# Sensor_Board_AS-3.net
KiCad netlist of a schematic drawn in EAGLE
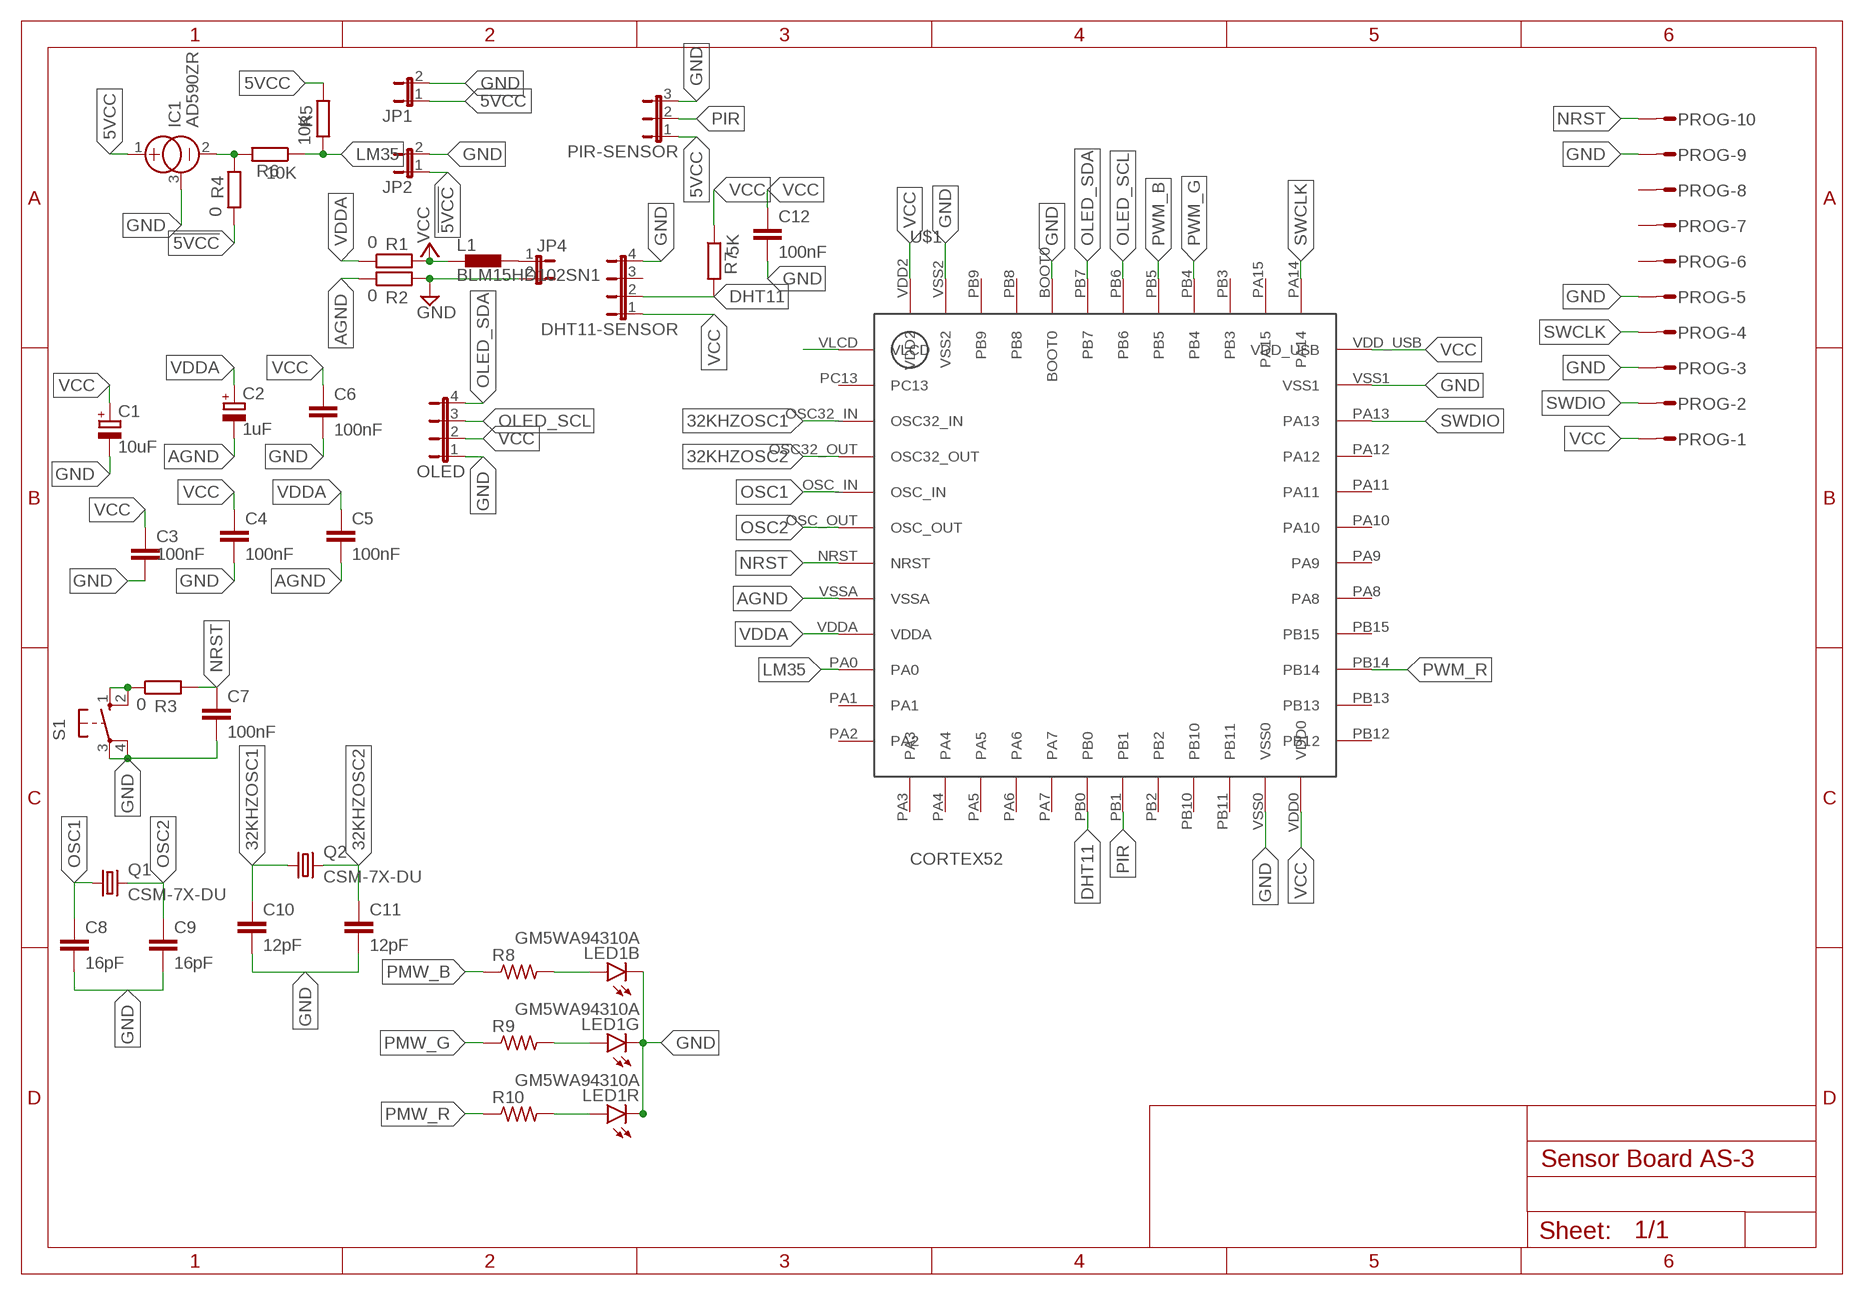
[diagram p0: schematic, sheet 1]

(export (version "E")
  (design (tool "Eeschema 10.0.6"))
  (components
    (comp (ref "C1")
      (value "10uF")
      (footprint "eagle-import:139CLL-2R")
      (libsource (lib "eagle-import") (part "CPOL-EU139CLL-2R"))
    )
    (comp (ref "C2")
      (value "1uF")
      (footprint "eagle-import:139CLL-2R")
      (libsource (lib "eagle-import") (part "CPOL-EU139CLL-2R"))
    )
    (comp (ref "C3")
      (value "100nF")
      (footprint "eagle-import:C0805")
      (libsource (lib "eagle-import") (part "C-EUC0805"))
    )
    (comp (ref "C4")
      (value "100nF")
      (footprint "eagle-import:C0805")
      (libsource (lib "eagle-import") (part "C-EUC0805"))
    )
    (comp (ref "C5")
      (value "100nF")
      (footprint "eagle-import:C0805")
      (libsource (lib "eagle-import") (part "C-EUC0805"))
    )
    (comp (ref "C6")
      (value "100nF")
      (footprint "eagle-import:C0805")
      (libsource (lib "eagle-import") (part "C-EUC0805"))
    )
    (comp (ref "C7")
      (value "100nF")
      (footprint "eagle-import:C0805")
      (libsource (lib "eagle-import") (part "C-EUC0805"))
    )
    (comp (ref "C8")
      (value "16pF")
      (footprint "eagle-import:C0805")
      (libsource (lib "eagle-import") (part "C-EUC0805"))
    )
    (comp (ref "C9")
      (value "16pF")
      (footprint "eagle-import:C0805")
      (libsource (lib "eagle-import") (part "C-EUC0805"))
    )
    (comp (ref "C10")
      (value "12pF")
      (footprint "eagle-import:C0805")
      (libsource (lib "eagle-import") (part "C-EUC0805"))
    )
    (comp (ref "C11")
      (value "12pF")
      (footprint "eagle-import:C0805")
      (libsource (lib "eagle-import") (part "C-EUC0805"))
    )
    (comp (ref "C12")
      (value "100nF")
      (footprint "eagle-import:C0805")
      (libsource (lib "eagle-import") (part "C-EUC0805"))
    )
    (comp (ref "DHT11-SENSOR")
      (value "JP4E")
      (footprint "eagle-import:JP4")
      (libsource (lib "eagle-import") (part "JP4E"))
    )
    (comp (ref "IC1")
      (value "AD590ZR")
      (footprint "eagle-import:TO92")
      (libsource (lib "eagle-import") (part "AD590ZR"))
    )
    (comp (ref "JP1")
      (value "JP1E")
      (footprint "eagle-import:JP1")
      (libsource (lib "eagle-import") (part "JP1E"))
    )
    (comp (ref "JP2")
      (value "JP1E")
      (footprint "eagle-import:JP1")
      (libsource (lib "eagle-import") (part "JP1E"))
    )
    (comp (ref "JP4")
      (value "JP1E")
      (footprint "eagle-import:JP1")
      (libsource (lib "eagle-import") (part "JP1E"))
    )
    (comp (ref "L1")
      (value "BLM15HD102SN1")
      (footprint "eagle-import:0402")
      (libsource (lib "eagle-import") (part "BLM15HD102SN1"))
    )
    (comp (ref "LED1")
      (value "GM5WA94310A")
      (footprint "eagle-import:GM5WA94310A")
      (libsource (lib "eagle-import") (part "GM5WA94310A"))
    )
    (comp (ref "OLED")
      (value "JP4E")
      (footprint "eagle-import:JP4")
      (libsource (lib "eagle-import") (part "JP4E"))
    )
    (comp (ref "PIR-SENSOR")
      (value "JP2E")
      (footprint "eagle-import:JP2")
      (libsource (lib "eagle-import") (part "JP2E"))
    )
    (comp (ref "PROG")
      (value "S10P")
      (footprint "eagle-import:S10P")
      (libsource (lib "eagle-import") (part "S10P"))
    )
    (comp (ref "Q1")
      (value "CSM-7X-DU")
      (footprint "eagle-import:CSM-7X-DU")
      (libsource (lib "eagle-import") (part "CSM-7X-DU"))
    )
    (comp (ref "Q2")
      (value "CSM-7X-DU")
      (footprint "eagle-import:CSM-7X-DU")
      (libsource (lib "eagle-import") (part "CSM-7X-DU"))
    )
    (comp (ref "R1")
      (value "0")
      (footprint "eagle-import:R0805")
      (libsource (lib "eagle-import") (part "R-EU_R0805"))
    )
    (comp (ref "R2")
      (value "0")
      (footprint "eagle-import:R0805")
      (libsource (lib "eagle-import") (part "R-EU_R0805"))
    )
    (comp (ref "R3")
      (value "0")
      (footprint "eagle-import:R0805")
      (libsource (lib "eagle-import") (part "R-EU_R0805"))
    )
    (comp (ref "R4")
      (value "0")
      (footprint "eagle-import:R0805")
      (libsource (lib "eagle-import") (part "R-EU_R0805"))
    )
    (comp (ref "R5")
      (value "10K")
      (footprint "eagle-import:R0805")
      (libsource (lib "eagle-import") (part "R-EU_R0805"))
    )
    (comp (ref "R6")
      (value "10K")
      (footprint "eagle-import:R0805")
      (libsource (lib "eagle-import") (part "R-EU_R0805"))
    )
    (comp (ref "R7")
      (value "5K")
      (footprint "eagle-import:R0805")
      (libsource (lib "eagle-import") (part "R-EU_R0805"))
    )
    (comp (ref "R8")
      (value "R-US_R0805")
      (footprint "eagle-import:R0805")
      (libsource (lib "eagle-import") (part "R-US_R0805"))
    )
    (comp (ref "R9")
      (value "R-US_R0805")
      (footprint "eagle-import:R0805")
      (libsource (lib "eagle-import") (part "R-US_R0805"))
    )
    (comp (ref "R10")
      (value "R-US_R0805")
      (footprint "eagle-import:R0805")
      (libsource (lib "eagle-import") (part "R-US_R0805"))
    )
    (comp (ref "S1")
      (value "10-XX")
      (footprint "eagle-import:B3F-10XX")
      (fields (field (name "MPN") "B3F-1000"))
      (libsource (lib "eagle-import") (part "10-XX"))
    )
    (comp (ref "U$1")
      (value "CORTEX52")
      (footprint "eagle-import:CORTEX52")
      (libsource (lib "eagle-import") (part "CORTEX52"))
    )
  )
  (nets
    (net (code "1") (name "/~{5VCC}") (class "Default")
      (node (ref "JP2") (pin "1") (pinfunction "1_1") (pintype "passive"))
      (node (ref "R4") (pin "1") (pinfunction "1_1") (pintype "passive"))
    )
    (net (code "2") (name "5VCC") (class "Default")
      (node (ref "IC1") (pin "1") (pinfunction "+_1") (pintype "input"))
      (node (ref "JP1") (pin "1") (pinfunction "1_1") (pintype "passive"))
      (node (ref "PIR-SENSOR") (pin "1") (pinfunction "1_1") (pintype "passive"))
      (node (ref "R5") (pin "2") (pinfunction "2_2") (pintype "passive"))
    )
    (net (code "3") (name "32KHZOSC1") (class "Default")
      (node (ref "C10") (pin "1") (pinfunction "1_1") (pintype "passive"))
      (node (ref "Q2") (pin "1") (pinfunction "1_1") (pintype "passive"))
      (node (ref "U$1") (pin "OSC32_IN") (pinfunction "OSC32_IN_OSC32_IN") (pintype "bidirectional"))
    )
    (net (code "4") (name "32KHZOSC2") (class "Default")
      (node (ref "C11") (pin "1") (pinfunction "1_1") (pintype "passive"))
      (node (ref "Q2") (pin "2") (pinfunction "2_2") (pintype "passive"))
      (node (ref "U$1") (pin "OSC32_OUT") (pinfunction "OSC32_OUT_OSC32_OUT") (pintype "bidirectional"))
    )
    (net (code "5") (name "AGND") (class "Default")
      (node (ref "C2") (pin "-") (pinfunction "-_-") (pintype "passive"))
      (node (ref "C5") (pin "2") (pinfunction "2_2") (pintype "passive"))
      (node (ref "R2") (pin "1") (pinfunction "1_1") (pintype "passive"))
      (node (ref "U$1") (pin "VSSA") (pinfunction "VSSA_VSSA") (pintype "bidirectional"))
    )
    (net (code "6") (name "DHT11") (class "Default")
      (node (ref "DHT11-SENSOR") (pin "2") (pinfunction "2_2") (pintype "passive"))
      (node (ref "R7") (pin "2") (pinfunction "2_2") (pintype "passive"))
      (node (ref "U$1") (pin "PB0") (pinfunction "PB0_PB0") (pintype "bidirectional"))
    )
    (net (code "7") (name "GND") (class "Default")
      (node (ref "C1") (pin "-") (pinfunction "-_-") (pintype "passive"))
      (node (ref "C10") (pin "2") (pinfunction "2_2") (pintype "passive"))
      (node (ref "C11") (pin "2") (pinfunction "2_2") (pintype "passive"))
      (node (ref "C12") (pin "2") (pinfunction "2_2") (pintype "passive"))
      (node (ref "C3") (pin "2") (pinfunction "2_2") (pintype "passive"))
      (node (ref "C4") (pin "2") (pinfunction "2_2") (pintype "passive"))
      (node (ref "C6") (pin "2") (pinfunction "2_2") (pintype "passive"))
      (node (ref "C7") (pin "2") (pinfunction "2_2") (pintype "passive"))
      (node (ref "C8") (pin "2") (pinfunction "2_2") (pintype "passive"))
      (node (ref "C9") (pin "2") (pinfunction "2_2") (pintype "passive"))
      (node (ref "DHT11-SENSOR") (pin "4") (pinfunction "4_4") (pintype "passive"))
      (node (ref "IC1") (pin "3") (pinfunction "CAN_3") (pintype "passive"))
      (node (ref "JP1") (pin "2") (pinfunction "2_2") (pintype "passive"))
      (node (ref "JP2") (pin "2") (pinfunction "2_2") (pintype "passive"))
      (node (ref "JP4") (pin "2") (pinfunction "2_2") (pintype "passive"))
      (node (ref "LED1") (pin "4") (pinfunction "C_4") (pintype "passive"))
      (node (ref "LED1") (pin "5") (pinfunction "C_5") (pintype "passive"))
      (node (ref "LED1") (pin "6") (pinfunction "C_6") (pintype "passive"))
      (node (ref "OLED") (pin "1") (pinfunction "1_1") (pintype "passive"))
      (node (ref "PIR-SENSOR") (pin "3") (pinfunction "3_3") (pintype "passive"))
      (node (ref "PROG") (pin "3") (pinfunction "S_3") (pintype "passive"))
      (node (ref "PROG") (pin "5") (pinfunction "S_5") (pintype "passive"))
      (node (ref "PROG") (pin "9") (pinfunction "S_9") (pintype "passive"))
      (node (ref "R2") (pin "2") (pinfunction "2_2") (pintype "passive"))
      (node (ref "S1") (pin "3") (pinfunction "P_3") (pintype "passive"))
      (node (ref "S1") (pin "4") (pinfunction "P1_4") (pintype "passive"))
      (node (ref "U$1") (pin "BOOT0") (pinfunction "BOOT0_BOOT0") (pintype "bidirectional"))
      (node (ref "U$1") (pin "VSS0") (pinfunction "VSS0_VSS0") (pintype "bidirectional"))
      (node (ref "U$1") (pin "VSS1") (pinfunction "VSS1_VSS1") (pintype "bidirectional"))
      (node (ref "U$1") (pin "VSS2") (pinfunction "VSS2_VSS2") (pintype "bidirectional"))
    )
    (net (code "8") (name "LM35") (class "Default")
      (node (ref "R5") (pin "1") (pinfunction "1_1") (pintype "passive"))
      (node (ref "R6") (pin "1") (pinfunction "1_1") (pintype "passive"))
      (node (ref "U$1") (pin "PA0") (pinfunction "PA0_PA0") (pintype "bidirectional"))
    )
    (net (code "9") (name "NRST") (class "Default")
      (node (ref "C7") (pin "1") (pinfunction "1_1") (pintype "passive"))
      (node (ref "PROG") (pin "10") (pinfunction "S_10") (pintype "passive"))
      (node (ref "R3") (pin "2") (pinfunction "2_2") (pintype "passive"))
      (node (ref "U$1") (pin "NRST") (pinfunction "NRST_NRST") (pintype "bidirectional"))
    )
    (net (code "10") (name "Net-(IC1--)") (class "Default")
      (node (ref "IC1") (pin "2") (pinfunction "-_2") (pintype "input"))
      (node (ref "R4") (pin "2") (pinfunction "2_2") (pintype "passive"))
      (node (ref "R6") (pin "2") (pinfunction "2_2") (pintype "passive"))
    )
    (net (code "11") (name "Net-(JP4-Pad1)") (class "Default")
      (node (ref "JP4") (pin "1") (pinfunction "1_1") (pintype "passive"))
      (node (ref "L1") (pin "2") (pinfunction "2_2") (pintype "passive"))
    )
    (net (code "12") (name "Net-(LED1A-A)") (class "Default")
      (node (ref "LED1") (pin "1") (pinfunction "A_1") (pintype "passive"))
      (node (ref "R8") (pin "2") (pinfunction "2_2") (pintype "passive"))
    )
    (net (code "13") (name "Net-(LED1B-A)") (class "Default")
      (node (ref "LED1") (pin "3") (pinfunction "A_3") (pintype "passive"))
      (node (ref "R9") (pin "2") (pinfunction "2_2") (pintype "passive"))
    )
    (net (code "14") (name "Net-(LED1C-A)") (class "Default")
      (node (ref "LED1") (pin "2") (pinfunction "A_2") (pintype "passive"))
      (node (ref "R10") (pin "2") (pinfunction "2_2") (pintype "passive"))
    )
    (net (code "15") (name "Net-(S1-S)") (class "Default")
      (node (ref "R3") (pin "1") (pinfunction "1_1") (pintype "passive"))
      (node (ref "S1") (pin "1") (pinfunction "S_1") (pintype "passive"))
      (node (ref "S1") (pin "2") (pinfunction "S1_2") (pintype "passive"))
    )
    (net (code "16") (name "OLED_SCL") (class "Default")
      (node (ref "OLED") (pin "3") (pinfunction "3_3") (pintype "passive"))
      (node (ref "U$1") (pin "PB6") (pinfunction "PB6_PB6") (pintype "bidirectional"))
    )
    (net (code "17") (name "OLED_SDA") (class "Default")
      (node (ref "OLED") (pin "4") (pinfunction "4_4") (pintype "passive"))
      (node (ref "U$1") (pin "PB7") (pinfunction "PB7_PB7") (pintype "bidirectional"))
    )
    (net (code "18") (name "OSC1") (class "Default")
      (node (ref "C8") (pin "1") (pinfunction "1_1") (pintype "passive"))
      (node (ref "Q1") (pin "1") (pinfunction "1_1") (pintype "passive"))
      (node (ref "U$1") (pin "OSC_IN") (pinfunction "OSC_IN_OSC_IN") (pintype "bidirectional"))
    )
    (net (code "19") (name "OSC2") (class "Default")
      (node (ref "C9") (pin "1") (pinfunction "1_1") (pintype "passive"))
      (node (ref "Q1") (pin "2") (pinfunction "2_2") (pintype "passive"))
      (node (ref "U$1") (pin "OSC_OUT") (pinfunction "OSC_OUT_OSC_OUT") (pintype "bidirectional"))
    )
    (net (code "20") (name "PIR") (class "Default")
      (node (ref "PIR-SENSOR") (pin "2") (pinfunction "2_2") (pintype "passive"))
      (node (ref "U$1") (pin "PB1") (pinfunction "PB1_PB1") (pintype "bidirectional"))
    )
    (net (code "21") (name "PMW_B") (class "Default")
      (node (ref "R8") (pin "1") (pinfunction "1_1") (pintype "passive"))
    )
    (net (code "22") (name "PMW_G") (class "Default")
      (node (ref "R9") (pin "1") (pinfunction "1_1") (pintype "passive"))
    )
    (net (code "23") (name "PMW_R") (class "Default")
      (node (ref "R10") (pin "1") (pinfunction "1_1") (pintype "passive"))
    )
    (net (code "24") (name "PWM_B") (class "Default")
      (node (ref "U$1") (pin "PB5") (pinfunction "PB5_PB5") (pintype "bidirectional"))
    )
    (net (code "25") (name "PWM_G") (class "Default")
      (node (ref "U$1") (pin "PB4") (pinfunction "PB4_PB4") (pintype "bidirectional"))
    )
    (net (code "26") (name "PWM_R") (class "Default")
      (node (ref "U$1") (pin "PB14") (pinfunction "PB14_PB14") (pintype "bidirectional"))
    )
    (net (code "27") (name "SWCLK") (class "Default")
      (node (ref "PROG") (pin "4") (pinfunction "S_4") (pintype "passive"))
      (node (ref "U$1") (pin "PA14") (pinfunction "PA14_PA14") (pintype "bidirectional"))
    )
    (net (code "28") (name "SWDIO") (class "Default")
      (node (ref "PROG") (pin "2") (pinfunction "S_2") (pintype "passive"))
      (node (ref "U$1") (pin "PA13") (pinfunction "PA13_PA13") (pintype "bidirectional"))
    )
    (net (code "29") (name "VCC") (class "Default")
      (node (ref "C1") (pin "+") (pinfunction "+_+") (pintype "passive"))
      (node (ref "C12") (pin "1") (pinfunction "1_1") (pintype "passive"))
      (node (ref "C3") (pin "1") (pinfunction "1_1") (pintype "passive"))
      (node (ref "C4") (pin "1") (pinfunction "1_1") (pintype "passive"))
      (node (ref "C6") (pin "1") (pinfunction "1_1") (pintype "passive"))
      (node (ref "DHT11-SENSOR") (pin "1") (pinfunction "1_1") (pintype "passive"))
      (node (ref "L1") (pin "1") (pinfunction "1_1") (pintype "passive"))
      (node (ref "OLED") (pin "2") (pinfunction "2_2") (pintype "passive"))
      (node (ref "PROG") (pin "1") (pinfunction "S_1") (pintype "passive"))
      (node (ref "R1") (pin "2") (pinfunction "2_2") (pintype "passive"))
      (node (ref "R7") (pin "1") (pinfunction "1_1") (pintype "passive"))
      (node (ref "U$1") (pin "VDD0") (pinfunction "VDD0_VDD0") (pintype "bidirectional"))
      (node (ref "U$1") (pin "VDD2") (pinfunction "VDD2_VDD2") (pintype "bidirectional"))
      (node (ref "U$1") (pin "VDD_USB") (pinfunction "VDD_USB_VDD_USB") (pintype "bidirectional"))
    )
    (net (code "30") (name "VDDA") (class "Default")
      (node (ref "C2") (pin "+") (pinfunction "+_+") (pintype "passive"))
      (node (ref "C5") (pin "1") (pinfunction "1_1") (pintype "passive"))
      (node (ref "R1") (pin "1") (pinfunction "1_1") (pintype "passive"))
      (node (ref "U$1") (pin "VDDA") (pinfunction "VDDA_VDDA") (pintype "bidirectional"))
    )
    (net (code "31") (name "unconnected-(DHT11-SENSOR-Pad3)") (class "Default")
      (node (ref "DHT11-SENSOR") (pin "3") (pinfunction "3_3") (pintype "passive"))
    )
    (net (code "32") (name "unconnected-(PROGG-S-Pad6)") (class "Default")
      (node (ref "PROG") (pin "6") (pinfunction "S_6") (pintype "passive"))
    )
    (net (code "33") (name "unconnected-(PROGH-S-Pad7)") (class "Default")
      (node (ref "PROG") (pin "7") (pinfunction "S_7") (pintype "passive"))
    )
    (net (code "34") (name "unconnected-(PROGI-S-Pad8)") (class "Default")
      (node (ref "PROG") (pin "8") (pinfunction "S_8") (pintype "passive"))
    )
    (net (code "35") (name "unconnected-(U$1-PadPA1)") (class "Default")
      (node (ref "U$1") (pin "PA1") (pinfunction "PA1_PA1") (pintype "bidirectional"))
    )
    (net (code "36") (name "unconnected-(U$1-PadPA2)") (class "Default")
      (node (ref "U$1") (pin "PA2") (pinfunction "PA2_PA2") (pintype "bidirectional"))
    )
    (net (code "37") (name "unconnected-(U$1-PadPA3)") (class "Default")
      (node (ref "U$1") (pin "PA3") (pinfunction "PA3_PA3") (pintype "bidirectional"))
    )
    (net (code "38") (name "unconnected-(U$1-PadPA4)") (class "Default")
      (node (ref "U$1") (pin "PA4") (pinfunction "PA4_PA4") (pintype "bidirectional"))
    )
    (net (code "39") (name "unconnected-(U$1-PadPA5)") (class "Default")
      (node (ref "U$1") (pin "PA5") (pinfunction "PA5_PA5") (pintype "bidirectional"))
    )
    (net (code "40") (name "unconnected-(U$1-PadPA6)") (class "Default")
      (node (ref "U$1") (pin "PA6") (pinfunction "PA6_PA6") (pintype "bidirectional"))
    )
    (net (code "41") (name "unconnected-(U$1-PadPA7)") (class "Default")
      (node (ref "U$1") (pin "PA7") (pinfunction "PA7_PA7") (pintype "bidirectional"))
    )
    (net (code "42") (name "unconnected-(U$1-PadPA8)") (class "Default")
      (node (ref "U$1") (pin "PA8") (pinfunction "PA8_PA8") (pintype "bidirectional"))
    )
    (net (code "43") (name "unconnected-(U$1-PadPA9)") (class "Default")
      (node (ref "U$1") (pin "PA9") (pinfunction "PA9_PA9") (pintype "bidirectional"))
    )
    (net (code "44") (name "unconnected-(U$1-PadPA10)") (class "Default")
      (node (ref "U$1") (pin "PA10") (pinfunction "PA10_PA10") (pintype "bidirectional"))
    )
    (net (code "45") (name "unconnected-(U$1-PadPA11)") (class "Default")
      (node (ref "U$1") (pin "PA11") (pinfunction "PA11_PA11") (pintype "bidirectional"))
    )
    (net (code "46") (name "unconnected-(U$1-PadPA12)") (class "Default")
      (node (ref "U$1") (pin "PA12") (pinfunction "PA12_PA12") (pintype "bidirectional"))
    )
    (net (code "47") (name "unconnected-(U$1-PadPA15)") (class "Default")
      (node (ref "U$1") (pin "PA15") (pinfunction "PA15_PA15") (pintype "bidirectional"))
    )
    (net (code "48") (name "unconnected-(U$1-PadPB2)") (class "Default")
      (node (ref "U$1") (pin "PB2") (pinfunction "PB2_PB2") (pintype "bidirectional"))
    )
    (net (code "49") (name "unconnected-(U$1-PadPB3)") (class "Default")
      (node (ref "U$1") (pin "PB3") (pinfunction "PB3_PB3") (pintype "bidirectional"))
    )
    (net (code "50") (name "unconnected-(U$1-PadPB8)") (class "Default")
      (node (ref "U$1") (pin "PB8") (pinfunction "PB8_PB8") (pintype "bidirectional"))
    )
    (net (code "51") (name "unconnected-(U$1-PadPB9)") (class "Default")
      (node (ref "U$1") (pin "PB9") (pinfunction "PB9_PB9") (pintype "bidirectional"))
    )
    (net (code "52") (name "unconnected-(U$1-PadPB10)") (class "Default")
      (node (ref "U$1") (pin "PB10") (pinfunction "PB10_PB10") (pintype "bidirectional"))
    )
    (net (code "53") (name "unconnected-(U$1-PadPB11)") (class "Default")
      (node (ref "U$1") (pin "PB11") (pinfunction "PB11_PB11") (pintype "bidirectional"))
    )
    (net (code "54") (name "unconnected-(U$1-PadPB12)") (class "Default")
      (node (ref "U$1") (pin "PB12") (pinfunction "PB12_PB12") (pintype "bidirectional"))
    )
    (net (code "55") (name "unconnected-(U$1-PadPB13)") (class "Default")
      (node (ref "U$1") (pin "PB13") (pinfunction "PB13_PB13") (pintype "bidirectional"))
    )
    (net (code "56") (name "unconnected-(U$1-PadPB15)") (class "Default")
      (node (ref "U$1") (pin "PB15") (pinfunction "PB15_PB15") (pintype "bidirectional"))
    )
    (net (code "57") (name "unconnected-(U$1-PadPC13)") (class "Default")
      (node (ref "U$1") (pin "PC13") (pinfunction "PC13_PC13") (pintype "bidirectional"))
    )
    (net (code "58") (name "unconnected-(U$1-PadVLCD)") (class "Default")
      (node (ref "U$1") (pin "VLCD") (pinfunction "VLCD_VLCD") (pintype "bidirectional"))
    )
  )
)
